# design.net
KiCad netlist of a schematic drawn in Altium Designer
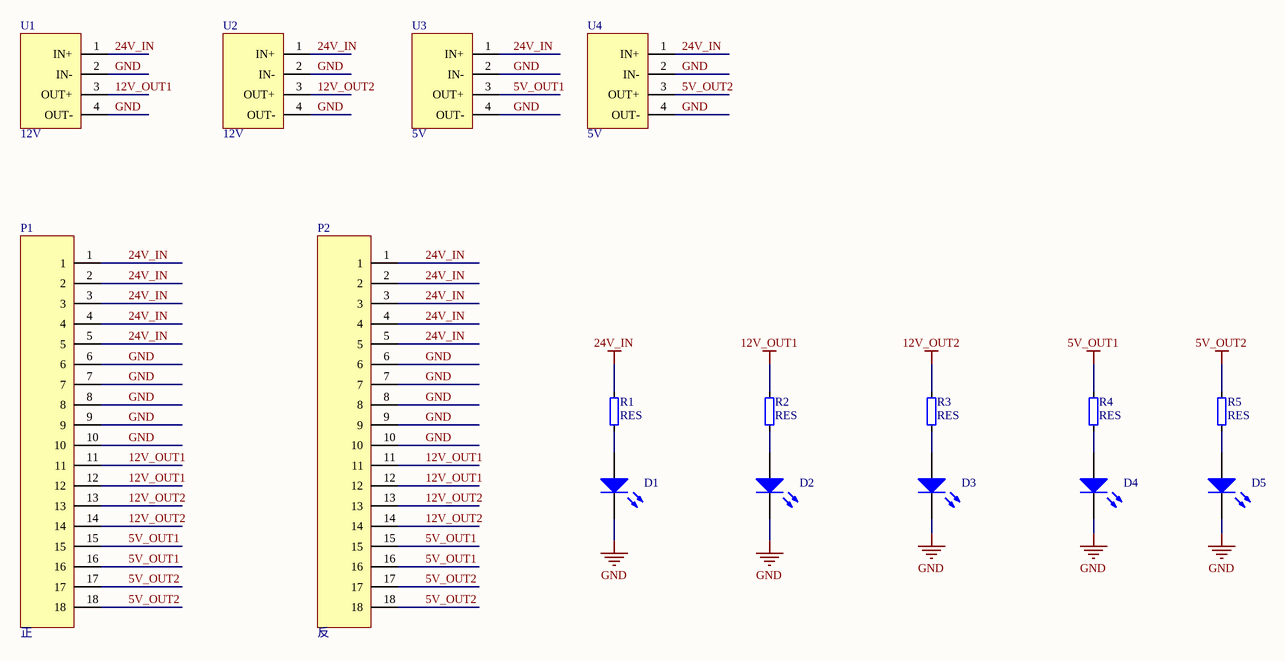
[diagram p0: 电源母板.SchDoc]

(export (version "E")
  (design (tool "Eeschema 10.0.6"))
  (components
    (comp (ref "D1")
      (value "D_LED 3MM")
      (footprint "0603_LED")
      (libsource (lib "常用小元件原理图库") (part "D_LED 3MM"))
    )
    (comp (ref "D2")
      (value "D_LED 3MM")
      (footprint "0603_LED")
      (libsource (lib "常用小元件原理图库") (part "D_LED 3MM"))
    )
    (comp (ref "D3")
      (value "D_LED 3MM")
      (footprint "0603_LED")
      (libsource (lib "常用小元件原理图库") (part "D_LED 3MM"))
    )
    (comp (ref "D4")
      (value "D_LED 3MM")
      (footprint "0603_LED")
      (libsource (lib "常用小元件原理图库") (part "D_LED 3MM"))
    )
    (comp (ref "D5")
      (value "D_LED 3MM")
      (footprint "0603_LED")
      (libsource (lib "常用小元件原理图库") (part "D_LED 3MM"))
    )
    (comp (ref "P1")
      (value "正")
      (footprint "1X16")
      (description "1X18")
      (libsource (lib "电源母板") (part "1X18"))
    )
    (comp (ref "P2")
      (value "反")
      (footprint "1X16")
      (description "1X18")
      (libsource (lib "电源母板") (part "1X18"))
    )
    (comp (ref "R1") (value "RES") (footprint "0603") (libsource (lib "常用小元件原理图库") (part "RES")))
    (comp (ref "R2") (value "RES") (footprint "0603") (libsource (lib "常用小元件原理图库") (part "RES")))
    (comp (ref "R3") (value "RES") (footprint "0603") (libsource (lib "常用小元件原理图库") (part "RES")))
    (comp (ref "R4") (value "RES") (footprint "0603") (libsource (lib "常用小元件原理图库") (part "RES")))
    (comp (ref "R5") (value "RES") (footprint "0603") (libsource (lib "常用小元件原理图库") (part "RES")))
    (comp (ref "U1")
      (value "12V")
      (footprint "LM2596稳压模块")
      (description "稳压模块")
      (libsource (lib "电源母板") (part "稳压模块"))
    )
    (comp (ref "U2")
      (value "12V")
      (footprint "LM2596稳压模块")
      (description "稳压模块")
      (libsource (lib "电源母板") (part "稳压模块"))
    )
    (comp (ref "U3")
      (value "5V")
      (footprint "LM2596稳压模块")
      (description "稳压模块")
      (libsource (lib "电源母板") (part "稳压模块"))
    )
    (comp (ref "U4")
      (value "5V")
      (footprint "LM2596稳压模块")
      (description "稳压模块")
      (libsource (lib "电源母板") (part "稳压模块"))
    )
  )
  (nets
    (net (code "1") (name "5V_OUT1") (class "Default")
      (node (ref "P1") (pin "15") (pinfunction "15_15") (pintype "passive"))
      (node (ref "P1") (pin "16") (pinfunction "16_16") (pintype "passive"))
      (node (ref "P2") (pin "15") (pinfunction "15_15") (pintype "passive"))
      (node (ref "P2") (pin "16") (pinfunction "16_16") (pintype "passive"))
      (node (ref "R4") (pin "2") (pinfunction "2_2") (pintype "passive"))
      (node (ref "U3") (pin "3") (pinfunction "OUT+_3") (pintype "passive"))
    )
    (net (code "2") (name "5V_OUT2") (class "Default")
      (node (ref "P1") (pin "17") (pinfunction "17_17") (pintype "passive"))
      (node (ref "P1") (pin "18") (pinfunction "18_18") (pintype "passive"))
      (node (ref "P2") (pin "17") (pinfunction "17_17") (pintype "passive"))
      (node (ref "P2") (pin "18") (pinfunction "18_18") (pintype "passive"))
      (node (ref "R5") (pin "2") (pinfunction "2_2") (pintype "passive"))
      (node (ref "U4") (pin "3") (pinfunction "OUT+_3") (pintype "passive"))
    )
    (net (code "3") (name "12V_OUT1") (class "Default")
      (node (ref "P1") (pin "11") (pinfunction "11_11") (pintype "passive"))
      (node (ref "P1") (pin "12") (pinfunction "12_12") (pintype "passive"))
      (node (ref "P2") (pin "11") (pinfunction "11_11") (pintype "passive"))
      (node (ref "P2") (pin "12") (pinfunction "12_12") (pintype "passive"))
      (node (ref "R2") (pin "2") (pinfunction "2_2") (pintype "passive"))
      (node (ref "U1") (pin "3") (pinfunction "OUT+_3") (pintype "passive"))
    )
    (net (code "4") (name "12V_OUT2") (class "Default")
      (node (ref "P1") (pin "13") (pinfunction "13_13") (pintype "passive"))
      (node (ref "P1") (pin "14") (pinfunction "14_14") (pintype "passive"))
      (node (ref "P2") (pin "13") (pinfunction "13_13") (pintype "passive"))
      (node (ref "P2") (pin "14") (pinfunction "14_14") (pintype "passive"))
      (node (ref "R3") (pin "2") (pinfunction "2_2") (pintype "passive"))
      (node (ref "U2") (pin "3") (pinfunction "OUT+_3") (pintype "passive"))
    )
    (net (code "5") (name "24V_IN") (class "Default")
      (node (ref "P1") (pin "1") (pinfunction "1_1") (pintype "passive"))
      (node (ref "P1") (pin "2") (pinfunction "2_2") (pintype "passive"))
      (node (ref "P1") (pin "3") (pinfunction "3_3") (pintype "passive"))
      (node (ref "P1") (pin "4") (pinfunction "4_4") (pintype "passive"))
      (node (ref "P1") (pin "5") (pinfunction "5_5") (pintype "passive"))
      (node (ref "P2") (pin "1") (pinfunction "1_1") (pintype "passive"))
      (node (ref "P2") (pin "2") (pinfunction "2_2") (pintype "passive"))
      (node (ref "P2") (pin "3") (pinfunction "3_3") (pintype "passive"))
      (node (ref "P2") (pin "4") (pinfunction "4_4") (pintype "passive"))
      (node (ref "P2") (pin "5") (pinfunction "5_5") (pintype "passive"))
      (node (ref "R1") (pin "2") (pinfunction "2_2") (pintype "passive"))
      (node (ref "U1") (pin "1") (pinfunction "IN+_1") (pintype "passive"))
      (node (ref "U2") (pin "1") (pinfunction "IN+_1") (pintype "passive"))
      (node (ref "U3") (pin "1") (pinfunction "IN+_1") (pintype "passive"))
      (node (ref "U4") (pin "1") (pinfunction "IN+_1") (pintype "passive"))
    )
    (net (code "6") (name "GND") (class "Default")
      (node (ref "D1") (pin "2") (pinfunction "K_2") (pintype "passive"))
      (node (ref "D2") (pin "2") (pinfunction "K_2") (pintype "passive"))
      (node (ref "D3") (pin "2") (pinfunction "K_2") (pintype "passive"))
      (node (ref "D4") (pin "2") (pinfunction "K_2") (pintype "passive"))
      (node (ref "D5") (pin "2") (pinfunction "K_2") (pintype "passive"))
      (node (ref "P1") (pin "10") (pinfunction "10_10") (pintype "passive"))
      (node (ref "P1") (pin "6") (pinfunction "6_6") (pintype "passive"))
      (node (ref "P1") (pin "7") (pinfunction "7_7") (pintype "passive"))
      (node (ref "P1") (pin "8") (pinfunction "8_8") (pintype "passive"))
      (node (ref "P1") (pin "9") (pinfunction "9_9") (pintype "passive"))
      (node (ref "P2") (pin "10") (pinfunction "10_10") (pintype "passive"))
      (node (ref "P2") (pin "6") (pinfunction "6_6") (pintype "passive"))
      (node (ref "P2") (pin "7") (pinfunction "7_7") (pintype "passive"))
      (node (ref "P2") (pin "8") (pinfunction "8_8") (pintype "passive"))
      (node (ref "P2") (pin "9") (pinfunction "9_9") (pintype "passive"))
      (node (ref "U1") (pin "2") (pinfunction "IN-_2") (pintype "passive"))
      (node (ref "U1") (pin "4") (pinfunction "OUT-_4") (pintype "passive"))
      (node (ref "U2") (pin "2") (pinfunction "IN-_2") (pintype "passive"))
      (node (ref "U2") (pin "4") (pinfunction "OUT-_4") (pintype "passive"))
      (node (ref "U3") (pin "2") (pinfunction "IN-_2") (pintype "passive"))
      (node (ref "U3") (pin "4") (pinfunction "OUT-_4") (pintype "passive"))
      (node (ref "U4") (pin "2") (pinfunction "IN-_2") (pintype "passive"))
      (node (ref "U4") (pin "4") (pinfunction "OUT-_4") (pintype "passive"))
    )
    (net (code "7") (name "Net-(D1-A)") (class "Default")
      (node (ref "D1") (pin "1") (pinfunction "A_1") (pintype "passive"))
      (node (ref "R1") (pin "1") (pinfunction "1_1") (pintype "passive"))
    )
    (net (code "8") (name "Net-(D2-A)") (class "Default")
      (node (ref "D2") (pin "1") (pinfunction "A_1") (pintype "passive"))
      (node (ref "R2") (pin "1") (pinfunction "1_1") (pintype "passive"))
    )
    (net (code "9") (name "Net-(D3-A)") (class "Default")
      (node (ref "D3") (pin "1") (pinfunction "A_1") (pintype "passive"))
      (node (ref "R3") (pin "1") (pinfunction "1_1") (pintype "passive"))
    )
    (net (code "10") (name "Net-(D4-A)") (class "Default")
      (node (ref "D4") (pin "1") (pinfunction "A_1") (pintype "passive"))
      (node (ref "R4") (pin "1") (pinfunction "1_1") (pintype "passive"))
    )
    (net (code "11") (name "Net-(D5-A)") (class "Default")
      (node (ref "D5") (pin "1") (pinfunction "A_1") (pintype "passive"))
      (node (ref "R5") (pin "1") (pinfunction "1_1") (pintype "passive"))
    )
  )
)
